# LoRa_ST_Sensor_Node_v1_3.net
KiCad netlist of a schematic drawn in EAGLE
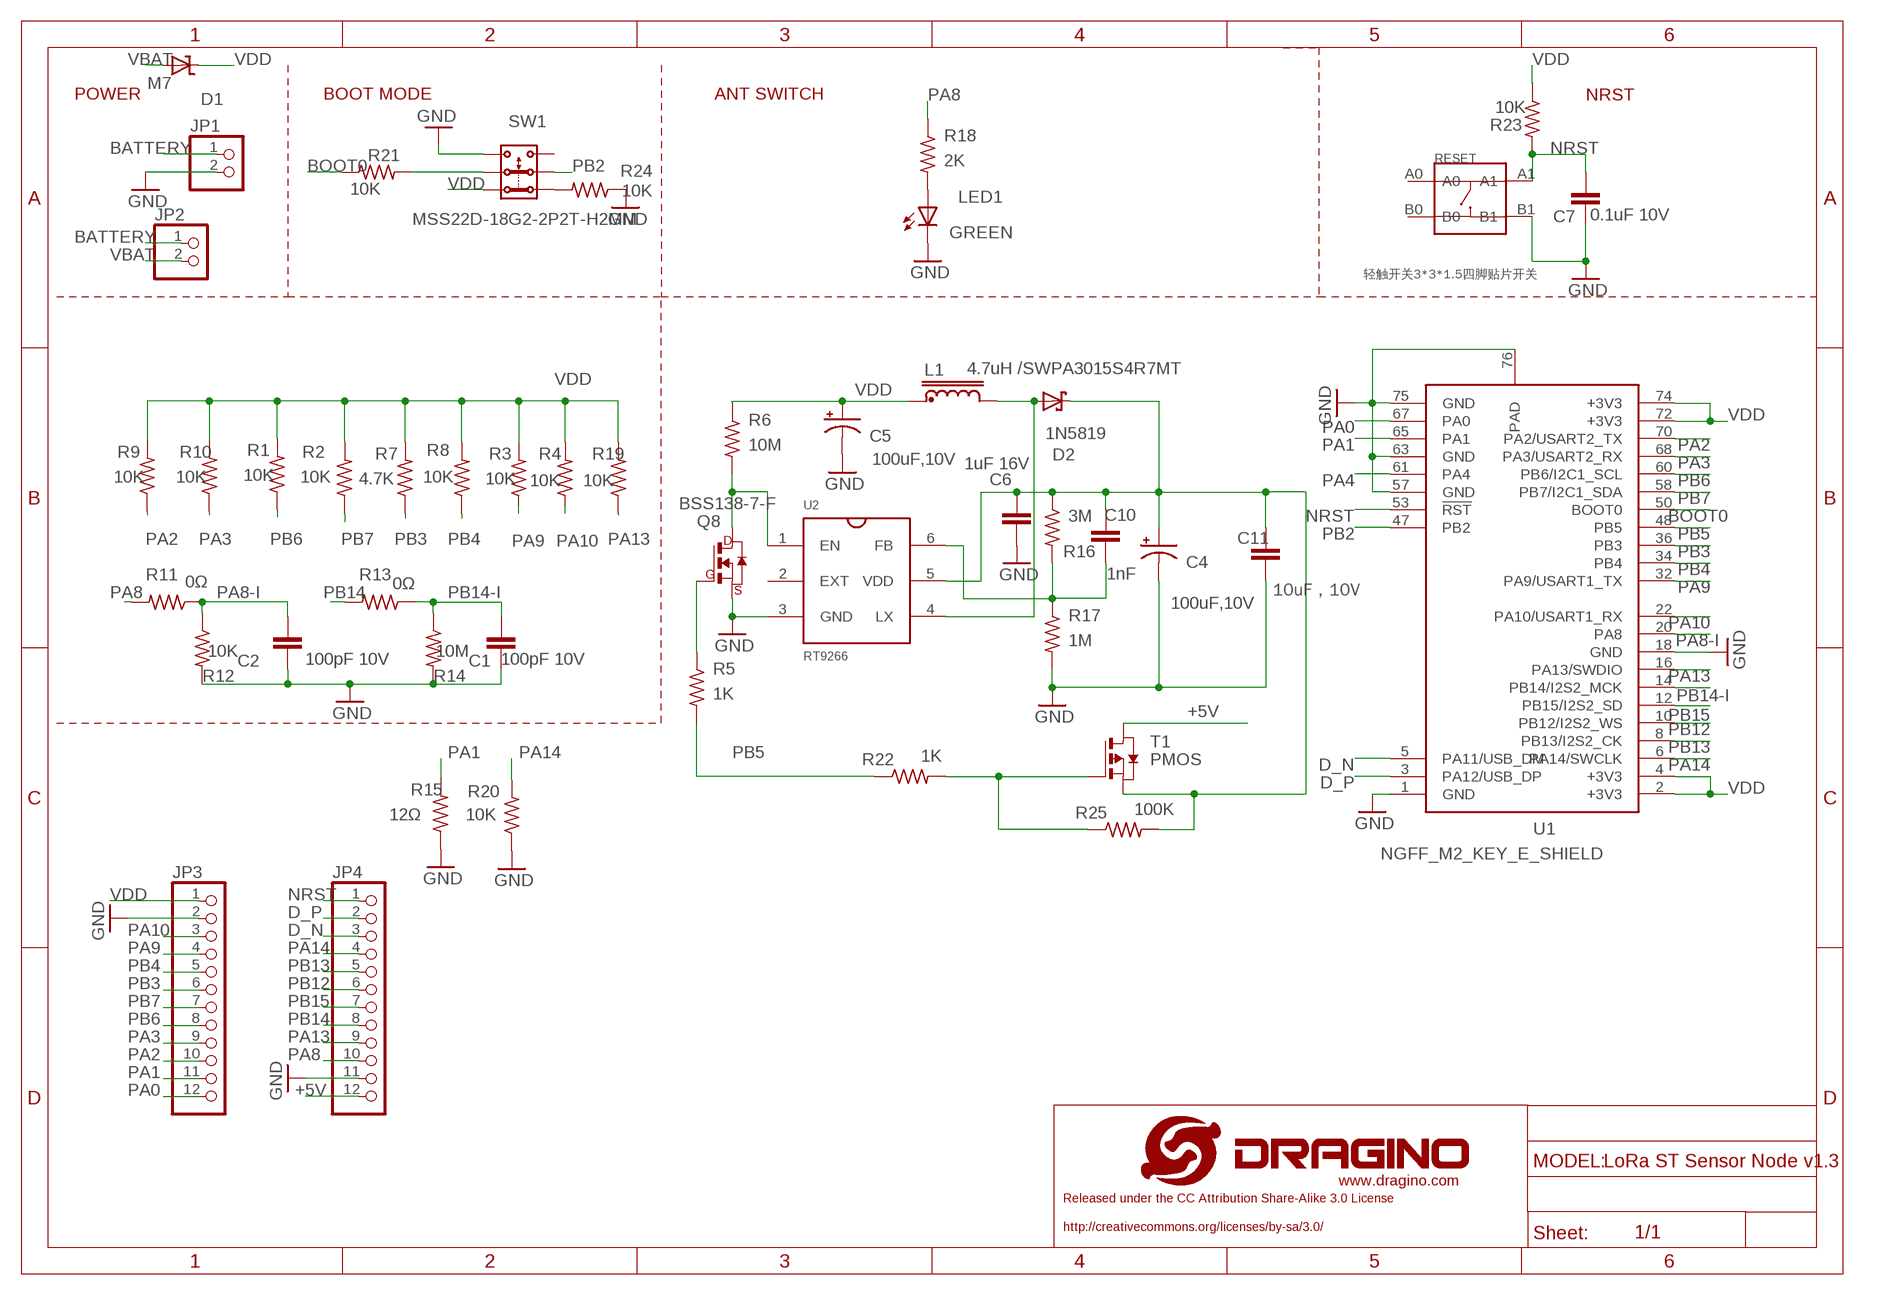
[diagram p0: schematic, sheet 1]

(export (version "E")
  (design (tool "Eeschema 10.0.6"))
  (components
    (comp (ref "C1")
      (value "100pF 10V")
      (footprint "eagle-import:C0603")
      (libsource (lib "eagle-import") (part "C-EUC0603"))
    )
    (comp (ref "C2")
      (value "100pF 10V")
      (footprint "eagle-import:C0603")
      (libsource (lib "eagle-import") (part "C-EUC0603"))
    )
    (comp (ref "C4")
      (value "100uF,10V")
      (footprint "eagle-import:SMC_B")
      (libsource (lib "eagle-import") (part "CPOL-USSMCB"))
    )
    (comp (ref "C5")
      (value "100uF,10V")
      (footprint "eagle-import:SMC_B")
      (libsource (lib "eagle-import") (part "CPOL-USSMCB"))
    )
    (comp (ref "C6")
      (value "1uF 16V")
      (footprint "eagle-import:C0603")
      (libsource (lib "eagle-import") (part "C-EUC0603"))
    )
    (comp (ref "C7")
      (value "0.1uF 10V")
      (footprint "eagle-import:C0402")
      (libsource (lib "eagle-import") (part "C-EUC0402"))
    )
    (comp (ref "C10")
      (value "1nF")
      (footprint "eagle-import:C0402")
      (libsource (lib "eagle-import") (part "C-EUC0402"))
    )
    (comp (ref "C11")
      (value "10uF，10V")
      (footprint "eagle-import:C0805")
      (libsource (lib "eagle-import") (part "dragino-passive_C-EUC0805"))
    )
    (comp (ref "D1")
      (value "M7")
      (footprint "eagle-import:DO214AC")
      (libsource (lib "eagle-import") (part "SCHOTTKYSMBG"))
    )
    (comp (ref "D2")
      (value "1N5819")
      (footprint "eagle-import:SOD123FL")
      (libsource (lib "eagle-import") (part "SMF5.0AT1"))
    )
    (comp (ref "JP1")
      (value "PINHD-1X2L")
      (footprint "eagle-import:XH2.54-2P-L")
      (libsource (lib "eagle-import") (part "PINHD-1X2L"))
    )
    (comp (ref "JP2")
      (value "PINHD-1X2")
      (footprint "eagle-import:1X02")
      (libsource (lib "eagle-import") (part "PINHD-1X2"))
    )
    (comp (ref "JP3")
      (value "PINHD-1X12\"\"")
      (footprint "eagle-import:1X12-DIP")
      (libsource (lib "eagle-import") (part "PINHD-1X12{dblquote}{dblquote}"))
    )
    (comp (ref "JP4")
      (value "PINHD-1X12\"\"")
      (footprint "eagle-import:1X12-DIP")
      (libsource (lib "eagle-import") (part "PINHD-1X12{dblquote}{dblquote}"))
    )
    (comp (ref "L1")
      (value "4.7uH /SWPA3015S4R7MT")
      (footprint "eagle-import:SWPA3010S")
      (libsource (lib "eagle-import") (part "INDUCTORSWPA3010S"))
    )
    (comp (ref "LED1")
      (value "GREEN")
      (footprint "eagle-import:CHIPLED_0603")
      (libsource (lib "eagle-import") (part "LEDCHIPLED_0603"))
    )
    (comp (ref "Q8")
      (value "BSS138-7-F")
      (footprint "eagle-import:SOT-23")
      (libsource (lib "eagle-import") (part "NMOSFET"))
    )
    (comp (ref "R1")
      (value "10K")
      (footprint "eagle-import:R0402")
      (libsource (lib "eagle-import") (part "R-US_R0402"))
    )
    (comp (ref "R2")
      (value "10K")
      (footprint "eagle-import:R0402")
      (libsource (lib "eagle-import") (part "R-US_R0402"))
    )
    (comp (ref "R3")
      (value "10K")
      (footprint "eagle-import:R0402")
      (libsource (lib "eagle-import") (part "R-US_R0402"))
    )
    (comp (ref "R4")
      (value "10K")
      (footprint "eagle-import:R0402")
      (libsource (lib "eagle-import") (part "R-US_R0402"))
    )
    (comp (ref "R5")
      (value "1K")
      (footprint "eagle-import:R0402")
      (libsource (lib "eagle-import") (part "R-US_R0402"))
    )
    (comp (ref "R6")
      (value "10M")
      (footprint "eagle-import:R0402")
      (libsource (lib "eagle-import") (part "R-US_R0402"))
    )
    (comp (ref "R7")
      (value "4.7K")
      (footprint "eagle-import:R0402")
      (libsource (lib "eagle-import") (part "R-US_R0402"))
    )
    (comp (ref "R8")
      (value "10K")
      (footprint "eagle-import:R0402")
      (libsource (lib "eagle-import") (part "R-US_R0402"))
    )
    (comp (ref "R9")
      (value "10K")
      (footprint "eagle-import:R0402")
      (libsource (lib "eagle-import") (part "R-US_R0402"))
    )
    (comp (ref "R10")
      (value "10K")
      (footprint "eagle-import:R0402")
      (libsource (lib "eagle-import") (part "R-US_R0402"))
    )
    (comp (ref "R11")
      (value "0Ω")
      (footprint "eagle-import:R0603")
      (libsource (lib "eagle-import") (part "R-US_R0603"))
    )
    (comp (ref "R12")
      (value "10K")
      (footprint "eagle-import:R0603")
      (libsource (lib "eagle-import") (part "R-US_R0603"))
    )
    (comp (ref "R13")
      (value "0Ω")
      (footprint "eagle-import:R0603")
      (libsource (lib "eagle-import") (part "R-US_R0603"))
    )
    (comp (ref "R14")
      (value "10M")
      (footprint "eagle-import:R0603")
      (libsource (lib "eagle-import") (part "R-US_R0603"))
    )
    (comp (ref "R15")
      (value "12Ω")
      (footprint "eagle-import:R1206")
      (libsource (lib "eagle-import") (part "R-US_R1206"))
    )
    (comp (ref "R16")
      (value "3M")
      (footprint "eagle-import:R0402")
      (libsource (lib "eagle-import") (part "R-US_R0402"))
    )
    (comp (ref "R17")
      (value "1M")
      (footprint "eagle-import:R0402")
      (libsource (lib "eagle-import") (part "R-US_R0402"))
    )
    (comp (ref "R18")
      (value "2K")
      (footprint "eagle-import:R0402")
      (libsource (lib "eagle-import") (part "R-US_R0402"))
    )
    (comp (ref "R19")
      (value "10K")
      (footprint "eagle-import:R0402")
      (libsource (lib "eagle-import") (part "R-US_R0402"))
    )
    (comp (ref "R20")
      (value "10K")
      (footprint "eagle-import:R0402")
      (libsource (lib "eagle-import") (part "R-US_R0402"))
    )
    (comp (ref "R21")
      (value "10K")
      (footprint "eagle-import:R0402")
      (libsource (lib "eagle-import") (part "R-US_R0402"))
    )
    (comp (ref "R22")
      (value "1K")
      (footprint "eagle-import:R0402")
      (libsource (lib "eagle-import") (part "R-US_R0402"))
    )
    (comp (ref "R23")
      (value "10K")
      (footprint "eagle-import:R0402")
      (libsource (lib "eagle-import") (part "R-US_R0402"))
    )
    (comp (ref "R24")
      (value "10K")
      (footprint "eagle-import:R0402")
      (libsource (lib "eagle-import") (part "R-US_R0402"))
    )
    (comp (ref "R25")
      (value "100K")
      (footprint "eagle-import:R0402")
      (libsource (lib "eagle-import") (part "R-US_R0402"))
    )
    (comp (ref "RESET")
      (value "轻触开关3*3*1.5四脚贴片开关")
      (footprint "eagle-import:SW4-SMD-3.35X3.35X1.5MM")
      (libsource (lib "eagle-import") (part "BUTTON-4P-3.3X3.3"))
    )
    (comp (ref "SW1")
      (value "MSS22D-18G2-2P2T-H2MM")
      (footprint "eagle-import:MSS22D-18G2-2P2T-H2MM-DIL")
      (libsource (lib "eagle-import") (part "MSS22D-18G2-2P2T-H2MM"))
    )
    (comp (ref "T1")
      (value "PMOS")
      (footprint "eagle-import:SOT-23")
      (libsource (lib "eagle-import") (part "PMOSSOT23"))
    )
    (comp (ref "U1")
      (value "NGFF_M2_KEY_E_SHIELD")
      (footprint "eagle-import:NGFF_M2_KEY_E_SHIELD")
      (libsource (lib "eagle-import") (part "NGFF_M2_KEY_E_SHIELD"))
    )
    (comp (ref "U2")
      (value "RT9266")
      (footprint "eagle-import:6_SOT-23")
      (libsource (lib "eagle-import") (part "RT9266"))
    )
  )
  (nets
    (net (code "1") (name "/+5V") (class "Default")
      (node (ref "JP4") (pin "12") (pinfunction "12_12") (pintype "passive"))
      (node (ref "T1") (pin "1") (pinfunction "D_1") (pintype "passive"))
    )
    (net (code "2") (name "/BATTERY") (class "Default")
      (node (ref "JP1") (pin "1") (pinfunction "1_1") (pintype "passive"))
      (node (ref "JP2") (pin "1") (pinfunction "1_1") (pintype "passive"))
    )
    (net (code "3") (name "/BOOT0") (class "Default")
      (node (ref "R21") (pin "1") (pinfunction "1_1") (pintype "passive"))
      (node (ref "U1") (pin "50") (pinfunction "BOOT0_50") (pintype "bidirectional"))
    )
    (net (code "4") (name "/D_N") (class "Default")
      (node (ref "JP4") (pin "3") (pinfunction "3_3") (pintype "passive"))
      (node (ref "U1") (pin "5") (pinfunction "PA11/USB_DM_5") (pintype "bidirectional"))
    )
    (net (code "5") (name "/D_P") (class "Default")
      (node (ref "JP4") (pin "2") (pinfunction "2_2") (pintype "passive"))
      (node (ref "U1") (pin "3") (pinfunction "PA12/USB_DP_3") (pintype "bidirectional"))
    )
    (net (code "6") (name "/NRST") (class "Default")
      (node (ref "C7") (pin "2") (pinfunction "2_2") (pintype "passive"))
      (node (ref "JP4") (pin "1") (pinfunction "1_1") (pintype "passive"))
      (node (ref "R23") (pin "2") (pinfunction "2_2") (pintype "passive"))
      (node (ref "RESET") (pin "A1") (pinfunction "A1_A1") (pintype "bidirectional"))
      (node (ref "U1") (pin "53") (pinfunction "~{RST}_53") (pintype "bidirectional"))
    )
    (net (code "7") (name "/PA0") (class "Default")
      (node (ref "JP3") (pin "12") (pinfunction "12_12") (pintype "passive"))
      (node (ref "U1") (pin "67") (pinfunction "PA0_67") (pintype "bidirectional"))
    )
    (net (code "8") (name "/PA1") (class "Default")
      (node (ref "JP3") (pin "11") (pinfunction "11_11") (pintype "passive"))
      (node (ref "R15") (pin "2") (pinfunction "2_2") (pintype "passive"))
      (node (ref "U1") (pin "65") (pinfunction "PA1_65") (pintype "bidirectional"))
    )
    (net (code "9") (name "/PA2") (class "Default")
      (node (ref "JP3") (pin "10") (pinfunction "10_10") (pintype "passive"))
      (node (ref "R9") (pin "1") (pinfunction "1_1") (pintype "passive"))
      (node (ref "U1") (pin "70") (pinfunction "PA2/USART2_TX_70") (pintype "bidirectional"))
    )
    (net (code "10") (name "/PA3") (class "Default")
      (node (ref "JP3") (pin "9") (pinfunction "9_9") (pintype "passive"))
      (node (ref "R10") (pin "1") (pinfunction "1_1") (pintype "passive"))
      (node (ref "U1") (pin "68") (pinfunction "PA3/USART2_RX_68") (pintype "bidirectional"))
    )
    (net (code "11") (name "/PA4") (class "Default")
      (node (ref "U1") (pin "61") (pinfunction "PA4_61") (pintype "bidirectional"))
    )
    (net (code "12") (name "/PA8") (class "Default")
      (node (ref "JP4") (pin "10") (pinfunction "10_10") (pintype "passive"))
      (node (ref "R11") (pin "2") (pinfunction "2_2") (pintype "passive"))
      (node (ref "R18") (pin "1") (pinfunction "1_1") (pintype "passive"))
    )
    (net (code "13") (name "/PA8-I") (class "Default")
      (node (ref "C2") (pin "2") (pinfunction "2_2") (pintype "passive"))
      (node (ref "R11") (pin "1") (pinfunction "1_1") (pintype "passive"))
      (node (ref "R12") (pin "1") (pinfunction "1_1") (pintype "passive"))
      (node (ref "U1") (pin "20") (pinfunction "PA8_20") (pintype "bidirectional"))
    )
    (net (code "14") (name "/PA9") (class "Default")
      (node (ref "JP3") (pin "4") (pinfunction "4_4") (pintype "passive"))
      (node (ref "R3") (pin "1") (pinfunction "1_1") (pintype "passive"))
      (node (ref "U1") (pin "32") (pinfunction "PA9/USART1_TX_32") (pintype "bidirectional"))
    )
    (net (code "15") (name "/PA10") (class "Default")
      (node (ref "JP3") (pin "3") (pinfunction "3_3") (pintype "passive"))
      (node (ref "R4") (pin "1") (pinfunction "1_1") (pintype "passive"))
      (node (ref "U1") (pin "22") (pinfunction "PA10/USART1_RX_22") (pintype "bidirectional"))
    )
    (net (code "16") (name "/PA13") (class "Default")
      (node (ref "JP4") (pin "9") (pinfunction "9_9") (pintype "passive"))
      (node (ref "R19") (pin "1") (pinfunction "1_1") (pintype "passive"))
      (node (ref "U1") (pin "16") (pinfunction "PA13/SWDIO_16") (pintype "bidirectional"))
    )
    (net (code "17") (name "/PA14") (class "Default")
      (node (ref "JP4") (pin "4") (pinfunction "4_4") (pintype "passive"))
      (node (ref "R20") (pin "2") (pinfunction "2_2") (pintype "passive"))
      (node (ref "U1") (pin "6") (pinfunction "PA14/SWCLK_6") (pintype "bidirectional"))
    )
    (net (code "18") (name "/PB2") (class "Default")
      (node (ref "SW1") (pin "5") (pinfunction "5_5") (pintype "bidirectional"))
      (node (ref "U1") (pin "47") (pinfunction "PB2_47") (pintype "bidirectional"))
    )
    (net (code "19") (name "/PB3") (class "Default")
      (node (ref "JP3") (pin "6") (pinfunction "6_6") (pintype "passive"))
      (node (ref "R7") (pin "1") (pinfunction "1_1") (pintype "passive"))
      (node (ref "U1") (pin "36") (pinfunction "PB3_36") (pintype "bidirectional"))
    )
    (net (code "20") (name "/PB4") (class "Default")
      (node (ref "JP3") (pin "5") (pinfunction "5_5") (pintype "passive"))
      (node (ref "R8") (pin "1") (pinfunction "1_1") (pintype "passive"))
      (node (ref "U1") (pin "34") (pinfunction "PB4_34") (pintype "bidirectional"))
    )
    (net (code "21") (name "/PB5") (class "Default")
      (node (ref "R22") (pin "1") (pinfunction "1_1") (pintype "passive"))
      (node (ref "R5") (pin "2") (pinfunction "2_2") (pintype "passive"))
      (node (ref "U1") (pin "48") (pinfunction "PB5_48") (pintype "bidirectional"))
    )
    (net (code "22") (name "/PB6") (class "Default")
      (node (ref "JP3") (pin "8") (pinfunction "8_8") (pintype "passive"))
      (node (ref "R1") (pin "1") (pinfunction "1_1") (pintype "passive"))
      (node (ref "U1") (pin "60") (pinfunction "PB6/I2C1_SCL_60") (pintype "bidirectional"))
    )
    (net (code "23") (name "/PB7") (class "Default")
      (node (ref "JP3") (pin "7") (pinfunction "7_7") (pintype "passive"))
      (node (ref "R2") (pin "1") (pinfunction "1_1") (pintype "passive"))
      (node (ref "U1") (pin "58") (pinfunction "PB7/I2C1_SDA_58") (pintype "bidirectional"))
    )
    (net (code "24") (name "/PB12") (class "Default")
      (node (ref "JP4") (pin "6") (pinfunction "6_6") (pintype "passive"))
      (node (ref "U1") (pin "10") (pinfunction "PB12/I2S2_WS_10") (pintype "bidirectional"))
    )
    (net (code "25") (name "/PB13") (class "Default")
      (node (ref "JP4") (pin "5") (pinfunction "5_5") (pintype "passive"))
      (node (ref "U1") (pin "8") (pinfunction "PB13/I2S2_CK_8") (pintype "bidirectional"))
    )
    (net (code "26") (name "/PB14") (class "Default")
      (node (ref "JP4") (pin "8") (pinfunction "8_8") (pintype "passive"))
      (node (ref "R13") (pin "2") (pinfunction "2_2") (pintype "passive"))
    )
    (net (code "27") (name "/PB14-I") (class "Default")
      (node (ref "C1") (pin "2") (pinfunction "2_2") (pintype "passive"))
      (node (ref "R13") (pin "1") (pinfunction "1_1") (pintype "passive"))
      (node (ref "R14") (pin "1") (pinfunction "1_1") (pintype "passive"))
      (node (ref "U1") (pin "14") (pinfunction "PB14/I2S2_MCK_14") (pintype "bidirectional"))
    )
    (net (code "28") (name "/PB15") (class "Default")
      (node (ref "JP4") (pin "7") (pinfunction "7_7") (pintype "passive"))
      (node (ref "U1") (pin "12") (pinfunction "PB15/I2S2_SD_12") (pintype "bidirectional"))
    )
    (net (code "29") (name "/VBAT") (class "Default")
      (node (ref "D1") (pin "A") (pinfunction "A_A") (pintype "passive"))
      (node (ref "JP2") (pin "2") (pinfunction "2_2") (pintype "passive"))
    )
    (net (code "30") (name "/VDD") (class "Default")
      (node (ref "C5") (pin "+") (pinfunction "+_+") (pintype "passive"))
      (node (ref "D1") (pin "C") (pinfunction "C_C") (pintype "passive"))
      (node (ref "JP3") (pin "1") (pinfunction "1_1") (pintype "passive"))
      (node (ref "L1") (pin "P$1") (pinfunction "1_P$1") (pintype "passive"))
      (node (ref "R1") (pin "2") (pinfunction "2_2") (pintype "passive"))
      (node (ref "R10") (pin "2") (pinfunction "2_2") (pintype "passive"))
      (node (ref "R19") (pin "2") (pinfunction "2_2") (pintype "passive"))
      (node (ref "R2") (pin "2") (pinfunction "2_2") (pintype "passive"))
      (node (ref "R23") (pin "1") (pinfunction "1_1") (pintype "passive"))
      (node (ref "R3") (pin "2") (pinfunction "2_2") (pintype "passive"))
      (node (ref "R4") (pin "2") (pinfunction "2_2") (pintype "passive"))
      (node (ref "R6") (pin "1") (pinfunction "1_1") (pintype "passive"))
      (node (ref "R7") (pin "2") (pinfunction "2_2") (pintype "passive"))
      (node (ref "R8") (pin "2") (pinfunction "2_2") (pintype "passive"))
      (node (ref "R9") (pin "2") (pinfunction "2_2") (pintype "passive"))
      (node (ref "SW1") (pin "3") (pinfunction "3_3") (pintype "bidirectional"))
      (node (ref "U1") (pin "2") (pinfunction "+3V3_2") (pintype "bidirectional"))
      (node (ref "U1") (pin "4") (pinfunction "+3V3_4") (pintype "bidirectional"))
      (node (ref "U1") (pin "72") (pinfunction "+3V3_72") (pintype "bidirectional"))
      (node (ref "U1") (pin "74") (pinfunction "+3V3_74") (pintype "bidirectional"))
    )
    (net (code "31") (name "GND") (class "Default")
      (node (ref "C1") (pin "1") (pinfunction "1_1") (pintype "passive"))
      (node (ref "C11") (pin "1") (pinfunction "1_1") (pintype "passive"))
      (node (ref "C2") (pin "1") (pinfunction "1_1") (pintype "passive"))
      (node (ref "C4") (pin "-") (pinfunction "-_-") (pintype "passive"))
      (node (ref "C5") (pin "-") (pinfunction "-_-") (pintype "passive"))
      (node (ref "C6") (pin "1") (pinfunction "1_1") (pintype "passive"))
      (node (ref "C7") (pin "1") (pinfunction "1_1") (pintype "passive"))
      (node (ref "JP1") (pin "2") (pinfunction "2_2") (pintype "passive"))
      (node (ref "JP3") (pin "2") (pinfunction "2_2") (pintype "passive"))
      (node (ref "JP4") (pin "11") (pinfunction "11_11") (pintype "passive"))
      (node (ref "LED1") (pin "C") (pinfunction "C_C") (pintype "passive"))
      (node (ref "Q8") (pin "2") (pinfunction "S_2") (pintype "passive"))
      (node (ref "R12") (pin "2") (pinfunction "2_2") (pintype "passive"))
      (node (ref "R14") (pin "2") (pinfunction "2_2") (pintype "passive"))
      (node (ref "R15") (pin "1") (pinfunction "1_1") (pintype "passive"))
      (node (ref "R17") (pin "2") (pinfunction "2_2") (pintype "passive"))
      (node (ref "R20") (pin "1") (pinfunction "1_1") (pintype "passive"))
      (node (ref "R24") (pin "1") (pinfunction "1_1") (pintype "passive"))
      (node (ref "RESET") (pin "B1") (pinfunction "B1_B1") (pintype "bidirectional"))
      (node (ref "SW1") (pin "1") (pinfunction "1_1") (pintype "bidirectional"))
      (node (ref "U1") (pin "1") (pinfunction "GND_1") (pintype "bidirectional"))
      (node (ref "U1") (pin "18") (pinfunction "GND_18") (pintype "bidirectional"))
      (node (ref "U1") (pin "57") (pinfunction "GND_57") (pintype "bidirectional"))
      (node (ref "U1") (pin "63") (pinfunction "GND_63") (pintype "bidirectional"))
      (node (ref "U1") (pin "75") (pinfunction "GND_75") (pintype "bidirectional"))
      (node (ref "U1") (pin "76") (pinfunction "PAD_76") (pintype "bidirectional"))
      (node (ref "U2") (pin "3") (pinfunction "GND_3") (pintype "bidirectional"))
    )
    (net (code "32") (name "Net-(L1-4)") (class "Default")
      (node (ref "D2") (pin "A") (pinfunction "A_A") (pintype "passive"))
      (node (ref "L1") (pin "P$2") (pinfunction "4_P$2") (pintype "passive"))
      (node (ref "U2") (pin "4") (pinfunction "LX_4") (pintype "bidirectional"))
    )
    (net (code "33") (name "Net-(LED1-PadA)") (class "Default")
      (node (ref "LED1") (pin "A") (pinfunction "A_A") (pintype "passive"))
      (node (ref "R18") (pin "2") (pinfunction "2_2") (pintype "passive"))
    )
    (net (code "34") (name "Net-(Q8-D)") (class "Default")
      (node (ref "Q8") (pin "1") (pinfunction "D_1") (pintype "passive"))
      (node (ref "R6") (pin "2") (pinfunction "2_2") (pintype "passive"))
      (node (ref "U2") (pin "1") (pinfunction "EN_1") (pintype "input"))
    )
    (net (code "35") (name "Net-(Q8-G)") (class "Default")
      (node (ref "Q8") (pin "3") (pinfunction "G_3") (pintype "passive"))
      (node (ref "R5") (pin "1") (pinfunction "1_1") (pintype "passive"))
    )
    (net (code "36") (name "Net-(R21-Pad2)") (class "Default")
      (node (ref "R21") (pin "2") (pinfunction "2_2") (pintype "passive"))
      (node (ref "SW1") (pin "2") (pinfunction "2_2") (pintype "bidirectional"))
    )
    (net (code "37") (name "Net-(R24-Pad2)") (class "Default")
      (node (ref "R24") (pin "2") (pinfunction "2_2") (pintype "passive"))
      (node (ref "SW1") (pin "4") (pinfunction "4_4") (pintype "bidirectional"))
    )
    (net (code "38") (name "Net-(T1-G)") (class "Default")
      (node (ref "R22") (pin "2") (pinfunction "2_2") (pintype "passive"))
      (node (ref "R25") (pin "1") (pinfunction "1_1") (pintype "passive"))
      (node (ref "T1") (pin "3") (pinfunction "G_3") (pintype "passive"))
    )
    (net (code "39") (name "Net-(T1-S)") (class "Default")
      (node (ref "C10") (pin "2") (pinfunction "2_2") (pintype "passive"))
      (node (ref "C11") (pin "2") (pinfunction "2_2") (pintype "passive"))
      (node (ref "C4") (pin "+") (pinfunction "+_+") (pintype "passive"))
      (node (ref "C6") (pin "2") (pinfunction "2_2") (pintype "passive"))
      (node (ref "D2") (pin "C") (pinfunction "C_C") (pintype "passive"))
      (node (ref "R16") (pin "1") (pinfunction "1_1") (pintype "passive"))
      (node (ref "R25") (pin "2") (pinfunction "2_2") (pintype "passive"))
      (node (ref "T1") (pin "2") (pinfunction "S_2") (pintype "passive"))
      (node (ref "U2") (pin "5") (pinfunction "VDD_5") (pintype "bidirectional"))
    )
    (net (code "40") (name "Net-(U2-FB)") (class "Default")
      (node (ref "C10") (pin "1") (pinfunction "1_1") (pintype "passive"))
      (node (ref "R16") (pin "2") (pinfunction "2_2") (pintype "passive"))
      (node (ref "R17") (pin "1") (pinfunction "1_1") (pintype "passive"))
      (node (ref "U2") (pin "6") (pinfunction "FB_6") (pintype "bidirectional"))
    )
    (net (code "41") (name "unconnected-(RESET-PadA0)") (class "Default")
      (node (ref "RESET") (pin "A0") (pinfunction "A0_A0") (pintype "bidirectional"))
    )
    (net (code "42") (name "unconnected-(RESET-PadB0)") (class "Default")
      (node (ref "RESET") (pin "B0") (pinfunction "B0_B0") (pintype "bidirectional"))
    )
    (net (code "43") (name "unconnected-(SW1-Pad6)") (class "Default")
      (node (ref "SW1") (pin "6") (pinfunction "6_6") (pintype "bidirectional"))
    )
    (net (code "44") (name "unconnected-(U2-EXT-Pad2)") (class "Default")
      (node (ref "U2") (pin "2") (pinfunction "EXT_2") (pintype "bidirectional"))
    )
  )
)
